# main.net
KiCad netlist of a schematic drawn in Altium Designer
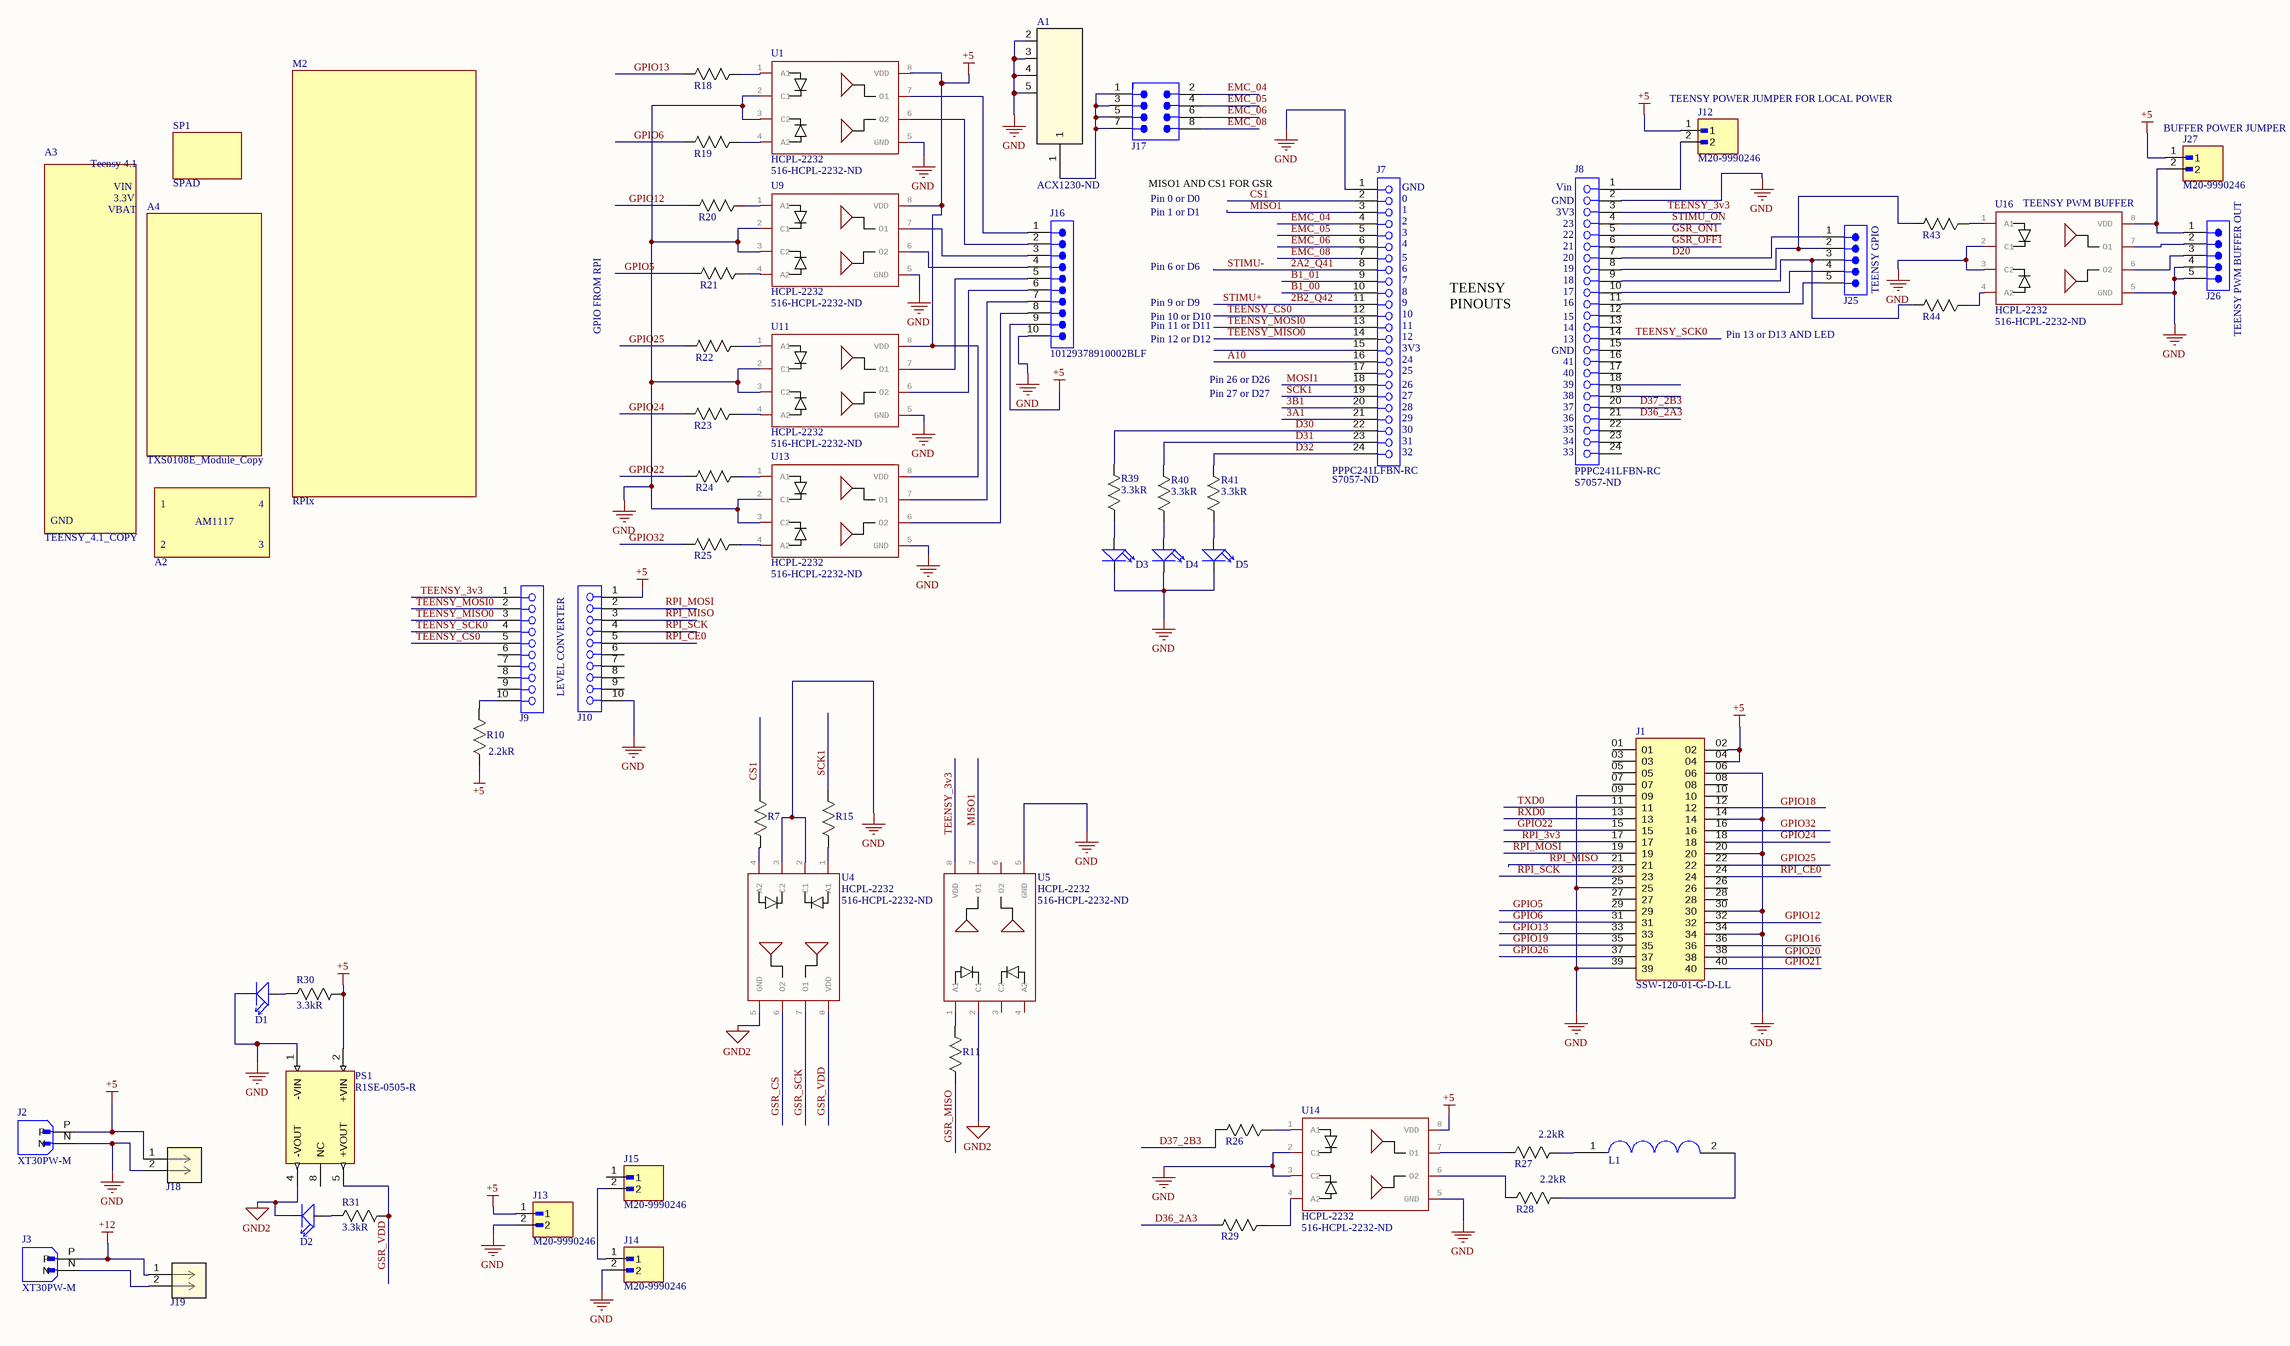
[diagram p0: main.SchDoc]

(export (version "E")
  (design (tool "Eeschema 10.0.6"))
  (components
    (comp (ref "A1")
      (value "SMA_VERTICAL")
      (footprint "SMA_VERTICAL")
      (description "connector, rf coaxial, sma str jack for p.c.board, 4 legs, .050 center cont, 50 ohm")
      (fields
        (field (name "MANUFACTURER") "Amphenol Connex")
        (field (name "MANUFACTURER PART NUMBER") "132134")
        (field (name "SUPPLIER PART NUMBER 1") "ACX1230-ND")
      )
      (libsource (lib "koncept") (part "SMA_VERTICAL"))
    )
    (comp (ref "A2")
      (value "AMS1117_BOARD_Copy")
      (footprint "AM117_BOARD_Copy")
      (libsource (lib "koncept") (part "AMS1117_BOARD_Copy"))
    )
    (comp (ref "A3")
      (value "TEENSY_4.1_COPY")
      (footprint "TEENSY_LONG_EXT_COPY")
      (fields (field (name "MF") "PJRC") (field (name "MP") "Teensy 4.1"))
      (libsource (lib "koncept") (part "TEENSY_4.1_COPY"))
    )
    (comp (ref "A4")
      (value "TXS0108E_Module_Copy")
      (footprint "TXS0108E_Module_Copy")
      (libsource (lib "koncept") (part "TXS0108E_Module_Copy"))
    )
    (comp (ref "D1")
      (value "LED")
      (footprint "LEDM1608X80")
      (description "Single Color LED, Ultra Bright Orange, Water Clear, 1.1mm")
      (fields
        (field (name "MANUFACTURER") "Vishay Lite-On")
        (field (name "MANUFACTURER PART NUMBER") "LTST-C190KFKT")
      )
      (libsource (lib "Passive") (part "LTST-C190KFKT_1"))
    )
    (comp (ref "D2")
      (value "LED")
      (footprint "LEDM1608X80")
      (description "Single Color LED, Ultra Bright Orange, Water Clear, 1.1mm")
      (fields
        (field (name "MANUFACTURER") "Vishay Lite-On")
        (field (name "MANUFACTURER PART NUMBER") "LTST-C190KFKT")
      )
      (libsource (lib "Passive") (part "LTST-C190KFKT_1"))
    )
    (comp (ref "D3")
      (value "LED")
      (footprint "LEDM1608X80")
      (description "Single Color LED, Ultra Bright Orange, Water Clear, 1.1mm")
      (fields
        (field (name "MANUFACTURER") "Vishay Lite-On")
        (field (name "MANUFACTURER PART NUMBER") "LTST-C190KFKT")
      )
      (libsource (lib "Passive") (part "LTST-C190KFKT_1"))
    )
    (comp (ref "D4")
      (value "LED")
      (footprint "LEDM1608X80")
      (description "Single Color LED, Ultra Bright Orange, Water Clear, 1.1mm")
      (fields
        (field (name "MANUFACTURER") "Vishay Lite-On")
        (field (name "MANUFACTURER PART NUMBER") "LTST-C190KFKT")
      )
      (libsource (lib "Passive") (part "LTST-C190KFKT_1"))
    )
    (comp (ref "D5")
      (value "LED")
      (footprint "LEDM1608X80")
      (description "Single Color LED, Ultra Bright Orange, Water Clear, 1.1mm")
      (fields
        (field (name "MANUFACTURER") "Vishay Lite-On")
        (field (name "MANUFACTURER PART NUMBER") "LTST-C190KFKT")
      )
      (libsource (lib "Passive") (part "LTST-C190KFKT_1"))
    )
    (comp (ref "J1")
      (value "SSW-120-01-G-D-LL")
      (footprint "SAMTEC_SSW-120-01-G-D-LL")
      (fields (field (name "MF") "Samtec Inc."))
      (libsource (lib "koncept") (part "SSW-120-01-G-D-LL"))
    )
    (comp (ref "J2")
      (value "XT30PW-M")
      (footprint "AMASS_XT30PW-M")
      (description "Socket; DC supply; XT30; male; PIN: 2; on PCBs; THT; Colour: yellow")
      (fields (field (name "MF") "AMASS"))
      (libsource (lib "koncept") (part "XT30PW-M"))
    )
    (comp (ref "J3")
      (value "XT30PW-M")
      (footprint "AMASS_XT30PW-M")
      (description "Socket; DC supply; XT30; male; PIN: 2; on PCBs; THT; Colour: yellow")
      (fields (field (name "MF") "AMASS"))
      (libsource (lib "koncept") (part "XT30PW-M"))
    )
    (comp (ref "J7")
      (value "PPPC241LFBN-RC")
      (footprint "HEADER_SOCKET_24")
      (description "Conn Hdr 24POS 0.1 Gold Pcb")
      (fields (field (name "MANUFACTURER") "Sullins") (field (name "SUPPLIER PART NUMBER 1") "S7057-ND"))
      (libsource (lib "Connectors") (part "HEADER_SOCKET_24"))
    )
    (comp (ref "J8")
      (value "PPPC241LFBN-RC")
      (footprint "HEADER_SOCKET_24")
      (description "Conn Hdr 24POS 0.1 Gold Pcb")
      (fields (field (name "MANUFACTURER") "Sullins") (field (name "SUPPLIER PART NUMBER 1") "S7057-ND"))
      (libsource (lib "Connectors") (part "HEADER_SOCKET_24"))
    )
    (comp (ref "J9")
      (value "PPTC101LFBN-RC")
      (footprint "HEADER_SOCKET_10")
      (description "10 Position Single Row 2.54 mm Pitch Vertical Through Hole Socket Header")
      (fields (field (name "MANUFACTURER") "Sullins"))
      (libsource (lib "Connectors") (part "HEADER_SOCKET_10"))
    )
    (comp (ref "J10")
      (value "PPTC101LFBN-RC")
      (footprint "HEADER_SOCKET_10")
      (description "10 Position Single Row 2.54 mm Pitch Vertical Through Hole Socket Header")
      (fields (field (name "MANUFACTURER") "Sullins"))
      (libsource (lib "Connectors") (part "HEADER_SOCKET_10"))
    )
    (comp (ref "J12")
      (value "M20-9990246")
      (footprint "HARWIN_M20-9990246")
      (description "2.54mm (0.1) Pitch SIL Vertical Throughboard Pin Header, 6.1mm mating pin height, tin, 2 contacts")
      (fields (field (name "MF") "Harwin"))
      (libsource (lib "koncept") (part "M20-9990246"))
    )
    (comp (ref "J13")
      (value "M20-9990246")
      (footprint "HARWIN_M20-9990246")
      (description "2.54mm (0.1) Pitch SIL Vertical Throughboard Pin Header, 6.1mm mating pin height, tin, 2 contacts")
      (fields (field (name "MF") "Harwin"))
      (libsource (lib "koncept") (part "M20-9990246"))
    )
    (comp (ref "J14")
      (value "M20-9990246")
      (footprint "HARWIN_M20-9990246")
      (description "2.54mm (0.1) Pitch SIL Vertical Throughboard Pin Header, 6.1mm mating pin height, tin, 2 contacts")
      (fields (field (name "MF") "Harwin"))
      (libsource (lib "koncept") (part "M20-9990246"))
    )
    (comp (ref "J15")
      (value "M20-9990246")
      (footprint "HARWIN_M20-9990246")
      (description "2.54mm (0.1) Pitch SIL Vertical Throughboard Pin Header, 6.1mm mating pin height, tin, 2 contacts")
      (fields (field (name "MF") "Harwin"))
      (libsource (lib "koncept") (part "M20-9990246"))
    )
    (comp (ref "J16")
      (value "10129378910002BLF")
      (footprint "HEADER_PIN_10")
      (description "Header Sr Vt Th 1X10-10129378-910002BLF")
      (fields (field (name "MANUFACTURER") "Amphenol ICC / FCI"))
      (libsource (lib "Connectors") (part "HEADER_PIN_10"))
    )
    (comp (ref "J17")
      (value "TSW-104-07-F-D")
      (footprint "HEADER_PIN_DOUBLE_8")
      (description "Connector, Header, 8Pos, 2Row, 2.54Mm Rohs Compliant: Yes")
      (fields (field (name "MANUFACTURER") "Samtec"))
      (libsource (lib "Connectors") (part "HEADER_PIN_DOUBLE_8"))
    )
    (comp (ref "J18")
      (value "B2P-VH")
      (footprint "CONN_B2P-VH_JST")
      (description "VH Non-RoHS Compliant 2003 Vertical Connector Header -25C~85C 10A 250V 0.303 7.70mm")
      (fields (field (name "MANUFACTURER") "JST"))
      (libsource (lib "Connectors") (part "B2P-VH"))
    )
    (comp (ref "J19")
      (value "B2P-VH")
      (footprint "CONN_B2P-VH_JST")
      (description "VH Non-RoHS Compliant 2003 Vertical Connector Header -25C~85C 10A 250V 0.303 7.70mm")
      (fields (field (name "MANUFACTURER") "JST"))
      (libsource (lib "Connectors") (part "B2P-VH"))
    )
    (comp (ref "J25")
      (value "61300511121")
      (footprint "HEADER_M_5")
      (description "THT Vertical Pin Header WR-PHD, Pitch 2.54 mm, Single Row, 5 pins")
      (fields (field (name "MANUFACTURER") "Wurth Electronics"))
      (libsource (lib "Connectors") (part "HEADER_M_5"))
    )
    (comp (ref "J26")
      (value "61300511121")
      (footprint "HEADER_M_5")
      (description "THT Vertical Pin Header WR-PHD, Pitch 2.54 mm, Single Row, 5 pins")
      (fields (field (name "MANUFACTURER") "Wurth Electronics"))
      (libsource (lib "Connectors") (part "HEADER_M_5"))
    )
    (comp (ref "J27")
      (value "M20-9990246")
      (footprint "HARWIN_M20-9990246")
      (description "2.54mm (0.1) Pitch SIL Vertical Throughboard Pin Header, 6.1mm mating pin height, tin, 2 contacts")
      (fields (field (name "MF") "Harwin"))
      (libsource (lib "koncept") (part "M20-9990246"))
    )
    (comp (ref "L1")
      (value "COIL_PLANNER_A")
      (footprint "COIL_PLANNER_A")
      (libsource (lib "koncept") (part "COIL_PLANNER_A"))
    )
    (comp (ref "M2")
      (value "RPIx")
      (footprint "MODULE_RASPBERRY_PI_3_COPY")
      (libsource (lib "koncept") (part "RPIx_Copy"))
    )
    (comp (ref "PS1")
      (value "R1SE-0505-R")
      (footprint "CONV_R1SE-0505-R")
      (description "1W DC/DC-Converter 'ECONOLINE' SMD 1kV unreg")
      (fields (field (name "MF") "Recom Power"))
      (libsource (lib "koncept") (part "R1SE-0505-R"))
    )
    (comp (ref "R7")
      (value "RMCF1206FT220R")
      (footprint "STA_RMCF1206_STP-L")
      (description "No Description Available")
      (fields (field (name "COPYRIGHT") "Copyright (C) 2025 Ultra Librarian. All rights reserved."))
      (libsource (lib "Passive") (part "RMCF1206FT220R"))
    )
    (comp (ref "R10")
      (value "CRGCQ1206F2K2")
      (footprint "STA_RMCF1206_STP-L")
      (description "SMD Chip Resistor, 2.2 kOhm, ± 1%, 250 mW, 1206 [3216 Metric], Thick Film, General Purpose")
      (fields (field (name "MANUFACTURER") "TE Connectivity") (field (name "RESISTANCE") "2.2kR"))
      (libsource (lib "Passive") (part "R1206F2K2"))
    )
    (comp (ref "R11")
      (value "RMCF1206FT220R")
      (footprint "STA_RMCF1206_STP-L")
      (description "No Description Available")
      (fields (field (name "COPYRIGHT") "Copyright (C) 2025 Ultra Librarian. All rights reserved."))
      (libsource (lib "Passive") (part "RMCF1206FT220R"))
    )
    (comp (ref "R15")
      (value "RMCF1206FT220R")
      (footprint "STA_RMCF1206_STP-L")
      (description "No Description Available")
      (fields (field (name "COPYRIGHT") "Copyright (C) 2025 Ultra Librarian. All rights reserved."))
      (libsource (lib "Passive") (part "RMCF1206FT220R"))
    )
    (comp (ref "R18")
      (value "RMCF1206FT220R")
      (footprint "STA_RMCF1206_STP-L")
      (description "No Description Available")
      (fields (field (name "COPYRIGHT") "Copyright (C) 2025 Ultra Librarian. All rights reserved."))
      (libsource (lib "Passive") (part "RMCF1206FT220R"))
    )
    (comp (ref "R19")
      (value "RMCF1206FT220R")
      (footprint "STA_RMCF1206_STP-L")
      (description "No Description Available")
      (fields (field (name "COPYRIGHT") "Copyright (C) 2025 Ultra Librarian. All rights reserved."))
      (libsource (lib "Passive") (part "RMCF1206FT220R"))
    )
    (comp (ref "R20")
      (value "RMCF1206FT220R")
      (footprint "STA_RMCF1206_STP-L")
      (description "No Description Available")
      (fields (field (name "COPYRIGHT") "Copyright (C) 2025 Ultra Librarian. All rights reserved."))
      (libsource (lib "Passive") (part "RMCF1206FT220R"))
    )
    (comp (ref "R21")
      (value "RMCF1206FT220R")
      (footprint "STA_RMCF1206_STP-L")
      (description "No Description Available")
      (fields (field (name "COPYRIGHT") "Copyright (C) 2025 Ultra Librarian. All rights reserved."))
      (libsource (lib "Passive") (part "RMCF1206FT220R"))
    )
    (comp (ref "R22")
      (value "RMCF1206FT220R")
      (footprint "STA_RMCF1206_STP-L")
      (description "No Description Available")
      (fields (field (name "COPYRIGHT") "Copyright (C) 2025 Ultra Librarian. All rights reserved."))
      (libsource (lib "Passive") (part "RMCF1206FT220R"))
    )
    (comp (ref "R23")
      (value "RMCF1206FT220R")
      (footprint "STA_RMCF1206_STP-L")
      (description "No Description Available")
      (fields (field (name "COPYRIGHT") "Copyright (C) 2025 Ultra Librarian. All rights reserved."))
      (libsource (lib "Passive") (part "RMCF1206FT220R"))
    )
    (comp (ref "R24")
      (value "RMCF1206FT220R")
      (footprint "STA_RMCF1206_STP-L")
      (description "No Description Available")
      (fields (field (name "COPYRIGHT") "Copyright (C) 2025 Ultra Librarian. All rights reserved."))
      (libsource (lib "Passive") (part "RMCF1206FT220R"))
    )
    (comp (ref "R25")
      (value "RMCF1206FT220R")
      (footprint "STA_RMCF1206_STP-L")
      (description "No Description Available")
      (fields (field (name "COPYRIGHT") "Copyright (C) 2025 Ultra Librarian. All rights reserved."))
      (libsource (lib "Passive") (part "RMCF1206FT220R"))
    )
    (comp (ref "R26")
      (value "RMCF1206FT220R")
      (footprint "STA_RMCF1206_STP-L")
      (description "No Description Available")
      (fields (field (name "COPYRIGHT") "Copyright (C) 2025 Ultra Librarian. All rights reserved."))
      (libsource (lib "Passive") (part "RMCF1206FT220R"))
    )
    (comp (ref "R27")
      (value "CRGCQ1206F2K2")
      (footprint "STA_RMCF1206_STP-L")
      (description "SMD Chip Resistor, 2.2 kOhm, ± 1%, 250 mW, 1206 [3216 Metric], Thick Film, General Purpose")
      (fields (field (name "MANUFACTURER") "TE Connectivity") (field (name "RESISTANCE") "2.2kR"))
      (libsource (lib "Passive") (part "R1206F2K2"))
    )
    (comp (ref "R28")
      (value "CRGCQ1206F2K2")
      (footprint "STA_RMCF1206_STP-L")
      (description "SMD Chip Resistor, 2.2 kOhm, ± 1%, 250 mW, 1206 [3216 Metric], Thick Film, General Purpose")
      (fields (field (name "MANUFACTURER") "TE Connectivity") (field (name "RESISTANCE") "2.2kR"))
      (libsource (lib "Passive") (part "R1206F2K2"))
    )
    (comp (ref "R29")
      (value "RMCF1206FT220R")
      (footprint "STA_RMCF1206_STP-L")
      (description "No Description Available")
      (fields (field (name "COPYRIGHT") "Copyright (C) 2025 Ultra Librarian. All rights reserved."))
      (libsource (lib "Passive") (part "RMCF1206FT220R"))
    )
    (comp (ref "R30")
      (value "CRG1206F3K3")
      (footprint "STA_RMCF1206_STP-L")
      (description "Res Thick Film 1206 3.3K Ohm 1% 0.25W(1/4W) ±100ppm/C Pad SMD T/R")
      (fields
        (field (name "MANUFACTURER") "TE Connectivity")
        (field (name "TOLERANCE") "1%")
        (field (name "RESISTANCE") "3.3kR")
      )
      (libsource (lib "Passive") (part "R3K3_1206"))
    )
    (comp (ref "R31")
      (value "CRG1206F3K3")
      (footprint "STA_RMCF1206_STP-L")
      (description "Res Thick Film 1206 3.3K Ohm 1% 0.25W(1/4W) ±100ppm/C Pad SMD T/R")
      (fields
        (field (name "MANUFACTURER") "TE Connectivity")
        (field (name "TOLERANCE") "1%")
        (field (name "RESISTANCE") "3.3kR")
      )
      (libsource (lib "Passive") (part "R3K3_1206"))
    )
    (comp (ref "R39")
      (value "CRG1206F3K3")
      (footprint "STA_RMCF1206_STP-L")
      (description "Res Thick Film 1206 3.3K Ohm 1% 0.25W(1/4W) ±100ppm/C Pad SMD T/R")
      (fields
        (field (name "MANUFACTURER") "TE Connectivity")
        (field (name "TOLERANCE") "1%")
        (field (name "RESISTANCE") "3.3kR")
      )
      (libsource (lib "Passive") (part "R3K3_1206"))
    )
    (comp (ref "R40")
      (value "CRG1206F3K3")
      (footprint "STA_RMCF1206_STP-L")
      (description "Res Thick Film 1206 3.3K Ohm 1% 0.25W(1/4W) ±100ppm/C Pad SMD T/R")
      (fields
        (field (name "MANUFACTURER") "TE Connectivity")
        (field (name "TOLERANCE") "1%")
        (field (name "RESISTANCE") "3.3kR")
      )
      (libsource (lib "Passive") (part "R3K3_1206"))
    )
    (comp (ref "R41")
      (value "CRG1206F3K3")
      (footprint "STA_RMCF1206_STP-L")
      (description "Res Thick Film 1206 3.3K Ohm 1% 0.25W(1/4W) ±100ppm/C Pad SMD T/R")
      (fields
        (field (name "MANUFACTURER") "TE Connectivity")
        (field (name "TOLERANCE") "1%")
        (field (name "RESISTANCE") "3.3kR")
      )
      (libsource (lib "Passive") (part "R3K3_1206"))
    )
    (comp (ref "R43")
      (value "RMCF1206FT220R")
      (footprint "STA_RMCF1206_STP-L")
      (description "No Description Available")
      (fields (field (name "COPYRIGHT") "Copyright (C) 2025 Ultra Librarian. All rights reserved."))
      (libsource (lib "Passive") (part "RMCF1206FT220R"))
    )
    (comp (ref "R44")
      (value "RMCF1206FT220R")
      (footprint "STA_RMCF1206_STP-L")
      (description "No Description Available")
      (fields (field (name "COPYRIGHT") "Copyright (C) 2025 Ultra Librarian. All rights reserved."))
      (libsource (lib "Passive") (part "RMCF1206FT220R"))
    )
    (comp (ref "SP1") (value "SPAD") (footprint "SPAD") (libsource (lib "koncept") (part "SPAD")))
    (comp (ref "U1")
      (value "HCPL-2232")
      (footprint "DIL08")
      (description "Optocoupler Logic Output Totem-Pole DC Input 2 Channel 8-Pin Plastic Dip Tube")
      (fields
        (field (name "MANUFACTURER") "Broadcom Avago")
        (field (name "SUPPLIER PART NUMBER 1") "516-HCPL-2232-ND")
      )
      (libsource (lib "koncept") (part "HCPL-2232"))
    )
    (comp (ref "U4")
      (value "HCPL-2232")
      (footprint "DIL08")
      (description "Optocoupler Logic Output Totem-Pole DC Input 2 Channel 8-Pin Plastic Dip Tube")
      (fields
        (field (name "MANUFACTURER") "Broadcom Avago")
        (field (name "SUPPLIER PART NUMBER 1") "516-HCPL-2232-ND")
      )
      (libsource (lib "koncept") (part "HCPL-2232"))
    )
    (comp (ref "U5")
      (value "HCPL-2232")
      (footprint "DIL08")
      (description "Optocoupler Logic Output Totem-Pole DC Input 2 Channel 8-Pin Plastic Dip Tube")
      (fields
        (field (name "MANUFACTURER") "Broadcom Avago")
        (field (name "SUPPLIER PART NUMBER 1") "516-HCPL-2232-ND")
      )
      (libsource (lib "koncept") (part "HCPL-2232"))
    )
    (comp (ref "U9")
      (value "HCPL-2232")
      (footprint "DIL08")
      (description "Optocoupler Logic Output Totem-Pole DC Input 2 Channel 8-Pin Plastic Dip Tube")
      (fields
        (field (name "MANUFACTURER") "Broadcom Avago")
        (field (name "SUPPLIER PART NUMBER 1") "516-HCPL-2232-ND")
      )
      (libsource (lib "koncept") (part "HCPL-2232"))
    )
    (comp (ref "U11")
      (value "HCPL-2232")
      (footprint "DIL08")
      (description "Optocoupler Logic Output Totem-Pole DC Input 2 Channel 8-Pin Plastic Dip Tube")
      (fields
        (field (name "MANUFACTURER") "Broadcom Avago")
        (field (name "SUPPLIER PART NUMBER 1") "516-HCPL-2232-ND")
      )
      (libsource (lib "koncept") (part "HCPL-2232"))
    )
    (comp (ref "U13")
      (value "HCPL-2232")
      (footprint "DIL08")
      (description "Optocoupler Logic Output Totem-Pole DC Input 2 Channel 8-Pin Plastic Dip Tube")
      (fields
        (field (name "MANUFACTURER") "Broadcom Avago")
        (field (name "SUPPLIER PART NUMBER 1") "516-HCPL-2232-ND")
      )
      (libsource (lib "koncept") (part "HCPL-2232"))
    )
    (comp (ref "U14")
      (value "HCPL-2232")
      (footprint "DIL08")
      (description "Optocoupler Logic Output Totem-Pole DC Input 2 Channel 8-Pin Plastic Dip Tube")
      (fields
        (field (name "MANUFACTURER") "Broadcom Avago")
        (field (name "SUPPLIER PART NUMBER 1") "516-HCPL-2232-ND")
      )
      (libsource (lib "koncept") (part "HCPL-2232"))
    )
    (comp (ref "U16")
      (value "HCPL-2232")
      (footprint "DIL08")
      (description "Optocoupler Logic Output Totem-Pole DC Input 2 Channel 8-Pin Plastic Dip Tube")
      (fields
        (field (name "MANUFACTURER") "Broadcom Avago")
        (field (name "SUPPLIER PART NUMBER 1") "516-HCPL-2232-ND")
      )
      (libsource (lib "koncept") (part "HCPL-2232"))
    )
  )
  (nets
    (net (code "1") (name "+5") (class "Default")
      (node (ref "J1") (pin "02") (pinfunction "02_02") (pintype "passive"))
      (node (ref "J1") (pin "04") (pinfunction "04_04") (pintype "passive"))
      (node (ref "J10") (pin "1") (pinfunction "1_1") (pintype "passive"))
      (node (ref "J12") (pin "1") (pinfunction "1_1") (pintype "passive"))
      (node (ref "J13") (pin "1") (pinfunction "1_1") (pintype "passive"))
      (node (ref "J16") (pin "9") (pinfunction "9_9") (pintype "passive"))
      (node (ref "J18") (pin "1") (pinfunction "1_1") (pintype "passive"))
      (node (ref "J2") (pin "P") (pinfunction "P_P") (pintype "power_in"))
      (node (ref "J27") (pin "1") (pinfunction "1_1") (pintype "passive"))
      (node (ref "PS1") (pin "2") (pinfunction "+VIN_2") (pintype "input"))
      (node (ref "R10") (pin "1") (pinfunction "1_1") (pintype "passive"))
      (node (ref "R30") (pin "2") (pinfunction "2_2") (pintype "passive"))
      (node (ref "U1") (pin "8") (pinfunction "VDD_8") (pintype "power_in"))
      (node (ref "U11") (pin "8") (pinfunction "VDD_8") (pintype "power_in"))
      (node (ref "U13") (pin "8") (pinfunction "VDD_8") (pintype "power_in"))
      (node (ref "U14") (pin "8") (pinfunction "VDD_8") (pintype "power_in"))
      (node (ref "U9") (pin "8") (pinfunction "VDD_8") (pintype "power_in"))
    )
    (net (code "2") (name "+12") (class "Default")
      (node (ref "J19") (pin "1") (pinfunction "1_1") (pintype "passive"))
      (node (ref "J3") (pin "P") (pinfunction "P_P") (pintype "power_in"))
    )
    (net (code "3") (name "/2A2_Q41") (class "Default")
      (node (ref "J7") (pin "8") (pinfunction "8_8") (pintype "passive"))
    )
    (net (code "4") (name "/2B2_Q42") (class "Default")
      (node (ref "J7") (pin "11") (pinfunction "11_11") (pintype "passive"))
    )
    (net (code "5") (name "/3A1") (class "Default")
      (node (ref "J7") (pin "21") (pinfunction "21_21") (pintype "passive"))
    )
    (net (code "6") (name "/3B1") (class "Default")
      (node (ref "J7") (pin "20") (pinfunction "20_20") (pintype "passive"))
    )
    (net (code "7") (name "/A10") (class "Default")
      (node (ref "J7") (pin "16") (pinfunction "16_16") (pintype "passive"))
    )
    (net (code "8") (name "/B1_00") (class "Default")
      (node (ref "J7") (pin "10") (pinfunction "10_10") (pintype "passive"))
    )
    (net (code "9") (name "/B1_01") (class "Default")
      (node (ref "J7") (pin "9") (pinfunction "9_9") (pintype "passive"))
    )
    (net (code "10") (name "/CS1") (class "Default")
      (node (ref "J7") (pin "2") (pinfunction "2_2") (pintype "passive"))
      (node (ref "R7") (pin "2") (pinfunction "2_2") (pintype "passive"))
    )
    (net (code "11") (name "/D20") (class "Default")
      (node (ref "J25") (pin "1") (pinfunction "1_1") (pintype "passive"))
      (node (ref "J8") (pin "7") (pinfunction "7_7") (pintype "passive"))
    )
    (net (code "12") (name "/D30") (class "Default")
      (node (ref "J7") (pin "22") (pinfunction "22_22") (pintype "passive"))
      (node (ref "R39") (pin "2") (pinfunction "2_2") (pintype "passive"))
    )
    (net (code "13") (name "/D31") (class "Default")
      (node (ref "J7") (pin "23") (pinfunction "23_23") (pintype "passive"))
      (node (ref "R40") (pin "2") (pinfunction "2_2") (pintype "passive"))
    )
    (net (code "14") (name "/D32") (class "Default")
      (node (ref "J7") (pin "24") (pinfunction "24_24") (pintype "passive"))
      (node (ref "R41") (pin "2") (pinfunction "2_2") (pintype "passive"))
    )
    (net (code "15") (name "/D36_2A3") (class "Default")
      (node (ref "J8") (pin "21") (pinfunction "21_21") (pintype "passive"))
      (node (ref "R29") (pin "2") (pinfunction "2_2") (pintype "passive"))
    )
    (net (code "16") (name "/D37_2B3") (class "Default")
      (node (ref "J8") (pin "20") (pinfunction "20_20") (pintype "passive"))
      (node (ref "R26") (pin "2") (pinfunction "2_2") (pintype "passive"))
    )
    (net (code "17") (name "/EMC_04") (class "Default")
      (node (ref "J17") (pin "2") (pinfunction "2_2") (pintype "passive"))
      (node (ref "J7") (pin "4") (pinfunction "4_4") (pintype "passive"))
    )
    (net (code "18") (name "/EMC_05") (class "Default")
      (node (ref "J17") (pin "4") (pinfunction "4_4") (pintype "passive"))
      (node (ref "J7") (pin "5") (pinfunction "5_5") (pintype "passive"))
    )
    (net (code "19") (name "/EMC_06") (class "Default")
      (node (ref "J17") (pin "6") (pinfunction "6_6") (pintype "passive"))
      (node (ref "J7") (pin "6") (pinfunction "6_6") (pintype "passive"))
    )
    (net (code "20") (name "/EMC_08") (class "Default")
      (node (ref "J17") (pin "8") (pinfunction "8_8") (pintype "passive"))
      (node (ref "J7") (pin "7") (pinfunction "7_7") (pintype "passive"))
    )
    (net (code "21") (name "/GPIO5") (class "Default")
      (node (ref "J1") (pin "29") (pinfunction "29_29") (pintype "passive"))
      (node (ref "R21") (pin "2") (pinfunction "2_2") (pintype "passive"))
    )
    (net (code "22") (name "/GPIO6") (class "Default")
      (node (ref "J1") (pin "31") (pinfunction "31_31") (pintype "passive"))
      (node (ref "R19") (pin "2") (pinfunction "2_2") (pintype "passive"))
    )
    (net (code "23") (name "/GPIO12") (class "Default")
      (node (ref "J1") (pin "32") (pinfunction "32_32") (pintype "passive"))
      (node (ref "R20") (pin "2") (pinfunction "2_2") (pintype "passive"))
    )
    (net (code "24") (name "/GPIO13") (class "Default")
      (node (ref "J1") (pin "33") (pinfunction "33_33") (pintype "passive"))
      (node (ref "R18") (pin "2") (pinfunction "2_2") (pintype "passive"))
    )
    (net (code "25") (name "/GPIO16") (class "Default")
      (node (ref "J1") (pin "36") (pinfunction "36_36") (pintype "passive"))
    )
    (net (code "27") (name "/GPIO19") (class "Default")
      (node (ref "J1") (pin "35") (pinfunction "35_35") (pintype "passive"))
    )
    (net (code "29") (name "/GPIO21") (class "Default")
      (node (ref "J1") (pin "40") (pinfunction "40_40") (pintype "passive"))
    )
    (net (code "30") (name "/GPIO22") (class "Default")
      (node (ref "J1") (pin "15") (pinfunction "15_15") (pintype "passive"))
      (node (ref "R24") (pin "2") (pinfunction "2_2") (pintype "passive"))
    )
    (net (code "31") (name "/GPIO24") (class "Default")
      (node (ref "J1") (pin "18") (pinfunction "18_18") (pintype "passive"))
      (node (ref "R23") (pin "2") (pinfunction "2_2") (pintype "passive"))
    )
    (net (code "32") (name "/GPIO25") (class "Default")
      (node (ref "J1") (pin "22") (pinfunction "22_22") (pintype "passive"))
      (node (ref "R22") (pin "2") (pinfunction "2_2") (pintype "passive"))
    )
    (net (code "33") (name "/GPIO26") (class "Default")
      (node (ref "J1") (pin "37") (pinfunction "37_37") (pintype "passive"))
    )
    (net (code "34") (name "/GPIO32") (class "Default")
      (node (ref "J1") (pin "16") (pinfunction "16_16") (pintype "passive"))
      (node (ref "R25") (pin "2") (pinfunction "2_2") (pintype "passive"))
    )
    (net (code "35") (name "/GSR_CS") (class "Default")
      (node (ref "U4") (pin "6") (pinfunction "O2_6") (pintype "power_in"))
    )
    (net (code "36") (name "/GSR_MISO") (class "Default")
      (node (ref "R11") (pin "1") (pinfunction "1_1") (pintype "passive"))
    )
    (net (code "37") (name "/GSR_OFF1") (class "Default")
      (node (ref "J8") (pin "6") (pinfunction "6_6") (pintype "passive"))
    )
    (net (code "38") (name "/GSR_ON1") (class "Default")
      (node (ref "J8") (pin "5") (pinfunction "5_5") (pintype "passive"))
    )
    (net (code "39") (name "/GSR_SCK") (class "Default")
      (node (ref "U4") (pin "7") (pinfunction "O1_7") (pintype "power_in"))
    )
    (net (code "40") (name "/GSR_VDD") (class "Default")
      (node (ref "PS1") (pin "5") (pinfunction "+VOUT_5") (pintype "output"))
      (node (ref "R31") (pin "2") (pinfunction "2_2") (pintype "passive"))
      (node (ref "U4") (pin "8") (pinfunction "VDD_8") (pintype "power_in"))
    )
    (net (code "41") (name "/MISO1") (class "Default")
      (node (ref "J7") (pin "3") (pinfunction "3_3") (pintype "passive"))
      (node (ref "U5") (pin "7") (pinfunction "O1_7") (pintype "power_in"))
    )
    (net (code "42") (name "/MOSI1") (class "Default")
      (node (ref "J7") (pin "18") (pinfunction "18_18") (pintype "passive"))
    )
    (net (code "43") (name "/RPI_3v3") (class "Default")
      (node (ref "J1") (pin "17") (pinfunction "17_17") (pintype "passive"))
    )
    (net (code "44") (name "/RPI_CE0") (class "Default")
      (node (ref "J1") (pin "24") (pinfunction "24_24") (pintype "passive"))
      (node (ref "J10") (pin "5") (pinfunction "5_5") (pintype "passive"))
    )
    (net (code "45") (name "/RPI_MISO") (class "Default")
      (node (ref "J1") (pin "21") (pinfunction "21_21") (pintype "passive"))
      (node (ref "J10") (pin "3") (pinfunction "3_3") (pintype "passive"))
    )
    (net (code "46") (name "/RPI_MOSI") (class "Default")
      (node (ref "J1") (pin "19") (pinfunction "19_19") (pintype "passive"))
      (node (ref "J10") (pin "2") (pinfunction "2_2") (pintype "passive"))
    )
    (net (code "47") (name "/RPI_SCK") (class "Default")
      (node (ref "J1") (pin "23") (pinfunction "23_23") (pintype "passive"))
      (node (ref "J10") (pin "4") (pinfunction "4_4") (pintype "passive"))
    )
    (net (code "48") (name "/RXD0") (class "Default")
      (node (ref "J1") (pin "13") (pinfunction "13_13") (pintype "passive"))
    )
    (net (code "49") (name "/SCK1") (class "Default")
      (node (ref "J7") (pin "19") (pinfunction "19_19") (pintype "passive"))
      (node (ref "R15") (pin "2") (pinfunction "2_2") (pintype "passive"))
    )
    (net (code "50") (name "/STIMU_ON") (class "Default")
      (node (ref "J8") (pin "4") (pinfunction "4_4") (pintype "passive"))
    )
    (net (code "51") (name "/TEENSY_3v3") (class "Default")
      (node (ref "J8") (pin "3") (pinfunction "3_3") (pintype "passive"))
      (node (ref "J9") (pin "1") (pinfunction "1_1") (pintype "passive"))
      (node (ref "U5") (pin "8") (pinfunction "VDD_8") (pintype "power_in"))
    )
    (net (code "52") (name "/TEENSY_CS0") (class "Default")
      (node (ref "J7") (pin "12") (pinfunction "12_12") (pintype "passive"))
      (node (ref "J9") (pin "5") (pinfunction "5_5") (pintype "passive"))
    )
    (net (code "53") (name "/TEENSY_MISO0") (class "Default")
      (node (ref "J7") (pin "14") (pinfunction "14_14") (pintype "passive"))
      (node (ref "J9") (pin "3") (pinfunction "3_3") (pintype "passive"))
    )
    (net (code "54") (name "/TEENSY_MOSI0") (class "Default")
      (node (ref "J7") (pin "13") (pinfunction "13_13") (pintype "passive"))
      (node (ref "J9") (pin "2") (pinfunction "2_2") (pintype "passive"))
    )
    (net (code "55") (name "/TEENSY_SCK0") (class "Default")
      (node (ref "J8") (pin "14") (pinfunction "14_14") (pintype "passive"))
      (node (ref "J9") (pin "4") (pinfunction "4_4") (pintype "passive"))
    )
    (net (code "56") (name "/TXD0") (class "Default")
      (node (ref "J1") (pin "11") (pinfunction "11_11") (pintype "passive"))
    )
    (net (code "57") (name "GND") (class "Default")
      (node (ref "A1") (pin "2") (pinfunction "2_2") (pintype "passive"))
      (node (ref "A1") (pin "3") (pinfunction "3_3") (pintype "passive"))
      (node (ref "A1") (pin "4") (pinfunction "4_4") (pintype "passive"))
      (node (ref "A1") (pin "5") (pinfunction "5_5") (pintype "passive"))
      (node (ref "D1") (pin "C") (pinfunction "C_C") (pintype "passive"))
      (node (ref "D3") (pin "C") (pinfunction "C_C") (pintype "passive"))
      (node (ref "D4") (pin "C") (pinfunction "C_C") (pintype "passive"))
      (node (ref "D5") (pin "C") (pinfunction "C_C") (pintype "passive"))
      (node (ref "J1") (pin "06") (pinfunction "06_06") (pintype "passive"))
      (node (ref "J1") (pin "09") (pinfunction "09_09") (pintype "passive"))
      (node (ref "J1") (pin "14") (pinfunction "14_14") (pintype "passive"))
      (node (ref "J1") (pin "20") (pinfunction "20_20") (pintype "passive"))
      (node (ref "J1") (pin "25") (pinfunction "25_25") (pintype "passive"))
      (node (ref "J1") (pin "30") (pinfunction "30_30") (pintype "passive"))
      (node (ref "J1") (pin "34") (pinfunction "34_34") (pintype "passive"))
      (node (ref "J1") (pin "39") (pinfunction "39_39") (pintype "passive"))
      (node (ref "J10") (pin "10") (pinfunction "10_10") (pintype "passive"))
      (node (ref "J13") (pin "2") (pinfunction "2_2") (pintype "passive"))
      (node (ref "J14") (pin "2") (pinfunction "2_2") (pintype "passive"))
      (node (ref "J16") (pin "10") (pinfunction "10_10") (pintype "passive"))
      (node (ref "J18") (pin "2") (pinfunction "2_2") (pintype "passive"))
      (node (ref "J2") (pin "N") (pinfunction "N_N") (pintype "power_in"))
      (node (ref "J26") (pin "4") (pinfunction "4_4") (pintype "passive"))
      (node (ref "J26") (pin "5") (pinfunction "5_5") (pintype "passive"))
      (node (ref "J7") (pin "1") (pinfunction "1_1") (pintype "passive"))
      (node (ref "J8") (pin "2") (pinfunction "2_2") (pintype "passive"))
      (node (ref "PS1") (pin "1") (pinfunction "-VIN_1") (pintype "input"))
      (node (ref "U1") (pin "2") (pinfunction "C1_2") (pintype "power_in"))
      (node (ref "U1") (pin "3") (pinfunction "C2_3") (pintype "power_in"))
      (node (ref "U1") (pin "5") (pinfunction "GND_5") (pintype "power_in"))
      (node (ref "U11") (pin "2") (pinfunction "C1_2") (pintype "power_in"))
      (node (ref "U11") (pin "3") (pinfunction "C2_3") (pintype "power_in"))
      (node (ref "U11") (pin "5") (pinfunction "GND_5") (pintype "power_in"))
      (node (ref "U13") (pin "2") (pinfunction "C1_2") (pintype "power_in"))
      (node (ref "U13") (pin "3") (pinfunction "C2_3") (pintype "power_in"))
      (node (ref "U13") (pin "5") (pinfunction "GND_5") (pintype "power_in"))
      (node (ref "U14") (pin "2") (pinfunction "C1_2") (pintype "power_in"))
      (node (ref "U14") (pin "3") (pinfunction "C2_3") (pintype "power_in"))
      (node (ref "U14") (pin "5") (pinfunction "GND_5") (pintype "power_in"))
      (node (ref "U16") (pin "2") (pinfunction "C1_2") (pintype "power_in"))
      (node (ref "U16") (pin "3") (pinfunction "C2_3") (pintype "power_in"))
      (node (ref "U16") (pin "5") (pinfunction "GND_5") (pintype "power_in"))
      (node (ref "U4") (pin "2") (pinfunction "C1_2") (pintype "power_in"))
      (node (ref "U4") (pin "3") (pinfunction "C2_3") (pintype "power_in"))
      (node (ref "U5") (pin "5") (pinfunction "GND_5") (pintype "power_in"))
      (node (ref "U9") (pin "2") (pinfunction "C1_2") (pintype "power_in"))
      (node (ref "U9") (pin "3") (pinfunction "C2_3") (pintype "power_in"))
      (node (ref "U9") (pin "5") (pinfunction "GND_5") (pintype "power_in"))
    )
    (net (code "58") (name "GND2") (class "Default")
      (node (ref "D2") (pin "C") (pinfunction "C_C") (pintype "passive"))
      (node (ref "PS1") (pin "4") (pinfunction "-VOUT_4") (pintype "output"))
      (node (ref "U4") (pin "5") (pinfunction "GND_5") (pintype "power_in"))
      (node (ref "U5") (pin "2") (pinfunction "C1_2") (pintype "power_in"))
    )
    (net (code "59") (name "Net-(A1-Pad1)") (class "Default")
      (node (ref "A1") (pin "1") (pinfunction "1_1") (pintype "passive"))
      (node (ref "J17") (pin "1") (pinfunction "1_1") (pintype "passive"))
      (node (ref "J17") (pin "3") (pinfunction "3_3") (pintype "passive"))
      (node (ref "J17") (pin "5") (pinfunction "5_5") (pintype "passive"))
      (node (ref "J17") (pin "7") (pinfunction "7_7") (pintype "passive"))
    )
    (net (code "60") (name "Net-(D1-PadA)") (class "Default")
      (node (ref "D1") (pin "A") (pinfunction "A_A") (pintype "passive"))
      (node (ref "R30") (pin "1") (pinfunction "1_1") (pintype "passive"))
    )
    (net (code "61") (name "Net-(D2-PadA)") (class "Default")
      (node (ref "D2") (pin "A") (pinfunction "A_A") (pintype "passive"))
      (node (ref "R31") (pin "1") (pinfunction "1_1") (pintype "passive"))
    )
    (net (code "62") (name "Net-(D3-PadA)") (class "Default")
      (node (ref "D3") (pin "A") (pinfunction "A_A") (pintype "passive"))
      (node (ref "R39") (pin "1") (pinfunction "1_1") (pintype "passive"))
    )
    (net (code "63") (name "Net-(D4-PadA)") (class "Default")
      (node (ref "D4") (pin "A") (pinfunction "A_A") (pintype "passive"))
      (node (ref "R40") (pin "1") (pinfunction "1_1") (pintype "passive"))
    )
    (net (code "64") (name "Net-(D5-PadA)") (class "Default")
      (node (ref "D5") (pin "A") (pinfunction "A_A") (pintype "passive"))
      (node (ref "R41") (pin "1") (pinfunction "1_1") (pintype "passive"))
    )
    (net (code "65") (name "Net-(J9-Pad10)") (class "Default")
      (node (ref "J9") (pin "10") (pinfunction "10_10") (pintype "passive"))
      (node (ref "R10") (pin "2") (pinfunction "2_2") (pintype "passive"))
    )
    (net (code "66") (name "Net-(J12-Pad2)") (class "Default")
      (node (ref "J12") (pin "2") (pinfunction "2_2") (pintype "passive"))
      (node (ref "J8") (pin "1") (pinfunction "1_1") (pintype "passive"))
    )
    (net (code "67") (name "Net-(J14-Pad1)") (class "Default")
      (node (ref "J14") (pin "1") (pinfunction "1_1") (pintype "passive"))
      (node (ref "J15") (pin "2") (pinfunction "2_2") (pintype "passive"))
    )
    (net (code "68") (name "Net-(J19-Pad2)") (class "Default")
      (node (ref "J19") (pin "2") (pinfunction "2_2") (pintype "passive"))
      (node (ref "J3") (pin "N") (pinfunction "N_N") (pintype "power_in"))
    )
    (net (code "69") (name "Net-(J25-Pad2)") (class "Default")
      (node (ref "J25") (pin "2") (pinfunction "2_2") (pintype "passive"))
      (node (ref "J8") (pin "8") (pinfunction "8_8") (pintype "passive"))
      (node (ref "R43") (pin "2") (pinfunction "2_2") (pintype "passive"))
    )
    (net (code "70") (name "Net-(J25-Pad3)") (class "Default")
      (node (ref "J25") (pin "3") (pinfunction "3_3") (pintype "passive"))
      (node (ref "J8") (pin "9") (pinfunction "9_9") (pintype "passive"))
      (node (ref "R44") (pin "2") (pinfunction "2_2") (pintype "passive"))
    )
    (net (code "71") (name "Net-(J25-Pad4)") (class "Default")
      (node (ref "J25") (pin "4") (pinfunction "4_4") (pintype "passive"))
      (node (ref "J8") (pin "10") (pinfunction "10_10") (pintype "passive"))
    )
    (net (code "72") (name "Net-(J25-Pad5)") (class "Default")
      (node (ref "J25") (pin "5") (pinfunction "5_5") (pintype "passive"))
      (node (ref "J8") (pin "11") (pinfunction "11_11") (pintype "passive"))
    )
    (net (code "73") (name "Net-(L1-Pad1)") (class "Default")
      (node (ref "L1") (pin "1") (pinfunction "1_1") (pintype "passive"))
      (node (ref "R27") (pin "2") (pinfunction "2_2") (pintype "passive"))
    )
    (net (code "74") (name "Net-(L1-Pad2)") (class "Default")
      (node (ref "L1") (pin "2") (pinfunction "2_2") (pintype "passive"))
      (node (ref "R28") (pin "2") (pinfunction "2_2") (pintype "passive"))
    )
    (net (code "75") (name "Net-(U1-A1)") (class "Default")
      (node (ref "R18") (pin "1") (pinfunction "1_1") (pintype "passive"))
      (node (ref "U1") (pin "1") (pinfunction "A1_1") (pintype "power_in"))
    )
    (net (code "76") (name "Net-(U1-A2)") (class "Default")
      (node (ref "R19") (pin "1") (pinfunction "1_1") (pintype "passive"))
      (node (ref "U1") (pin "4") (pinfunction "A2_4") (pintype "power_in"))
    )
    (net (code "77") (name "Net-(U1-O1)") (class "Default")
      (node (ref "J16") (pin "1") (pinfunction "1_1") (pintype "passive"))
      (node (ref "U1") (pin "7") (pinfunction "O1_7") (pintype "power_in"))
    )
    (net (code "78") (name "Net-(U1-O2)") (class "Default")
      (node (ref "J16") (pin "2") (pinfunction "2_2") (pintype "passive"))
      (node (ref "U1") (pin "6") (pinfunction "O2_6") (pintype "power_in"))
    )
    (net (code "79") (name "Net-(U4-A1)") (class "Default")
      (node (ref "R15") (pin "1") (pinfunction "1_1") (pintype "passive"))
      (node (ref "U4") (pin "1") (pinfunction "A1_1") (pintype "power_in"))
    )
    (net (code "80") (name "Net-(U4-A2)") (class "Default")
      (node (ref "R7") (pin "1") (pinfunction "1_1") (pintype "passive"))
      (node (ref "U4") (pin "4") (pinfunction "A2_4") (pintype "power_in"))
    )
    (net (code "81") (name "Net-(U5-A1)") (class "Default")
      (node (ref "R11") (pin "2") (pinfunction "2_2") (pintype "passive"))
      (node (ref "U5") (pin "1") (pinfunction "A1_1") (pintype "power_in"))
    )
    (net (code "82") (name "Net-(U9-A1)") (class "Default")
      (node (ref "R20") (pin "1") (pinfunction "1_1") (pintype "passive"))
      (node (ref "U9") (pin "1") (pinfunction "A1_1") (pintype "power_in"))
    )
    (net (code "83") (name "Net-(U9-A2)") (class "Default")
      (node (ref "R21") (pin "1") (pinfunction "1_1") (pintype "passive"))
      (node (ref "U9") (pin "4") (pinfunction "A2_4") (pintype "power_in"))
    )
    (net (code "84") (name "Net-(U9-O1)") (class "Default")
      (node (ref "J16") (pin "3") (pinfunction "3_3") (pintype "passive"))
      (node (ref "U9") (pin "7") (pinfunction "O1_7") (pintype "power_in"))
    )
    (net (code "85") (name "Net-(U9-O2)") (class "Default")
      (node (ref "J16") (pin "4") (pinfunction "4_4") (pintype "passive"))
      (node (ref "U9") (pin "6") (pinfunction "O2_6") (pintype "power_in"))
    )
    (net (code "86") (name "Net-(U11-A1)") (class "Default")
      (node (ref "R22") (pin "1") (pinfunction "1_1") (pintype "passive"))
      (node (ref "U11") (pin "1") (pinfunction "A1_1") (pintype "power_in"))
    )
    (net (code "87") (name "Net-(U11-A2)") (class "Default")
      (node (ref "R23") (pin "1") (pinfunction "1_1") (pintype "passive"))
      (node (ref "U11") (pin "4") (pinfunction "A2_4") (pintype "power_in"))
    )
    (net (code "88") (name "Net-(U11-O1)") (class "Default")
      (node (ref "J16") (pin "5") (pinfunction "5_5") (pintype "passive"))
      (node (ref "U11") (pin "7") (pinfunction "O1_7") (pintype "power_in"))
    )
    (net (code "89") (name "Net-(U11-O2)") (class "Default")
      (node (ref "J16") (pin "6") (pinfunction "6_6") (pintype "passive"))
      (node (ref "U11") (pin "6") (pinfunction "O2_6") (pintype "power_in"))
    )
    (net (code "90") (name "Net-(U13-A1)") (class "Default")
      (node (ref "R24") (pin "1") (pinfunction "1_1") (pintype "passive"))
      (node (ref "U13") (pin "1") (pinfunction "A1_1") (pintype "power_in"))
    )
    (net (code "91") (name "Net-(U13-A2)") (class "Default")
      (node (ref "R25") (pin "1") (pinfunction "1_1") (pintype "passive"))
      (node (ref "U13") (pin "4") (pinfunction "A2_4") (pintype "power_in"))
    )
    (net (code "92") (name "Net-(U13-O1)") (class "Default")
      (node (ref "J16") (pin "7") (pinfunction "7_7") (pintype "passive"))
      (node (ref "U13") (pin "7") (pinfunction "O1_7") (pintype "power_in"))
    )
    (net (code "93") (name "Net-(U13-O2)") (class "Default")
      (node (ref "J16") (pin "8") (pinfunction "8_8") (pintype "passive"))
      (node (ref "U13") (pin "6") (pinfunction "O2_6") (pintype "power_in"))
    )
    (net (code "94") (name "Net-(U14-A1)") (class "Default")
      (node (ref "R26") (pin "1") (pinfunction "1_1") (pintype "passive"))
      (node (ref "U14") (pin "1") (pinfunction "A1_1") (pintype "power_in"))
    )
    (net (code "95") (name "Net-(U14-A2)") (class "Default")
      (node (ref "R29") (pin "1") (pinfunction "1_1") (pintype "passive"))
      (node (ref "U14") (pin "4") (pinfunction "A2_4") (pintype "power_in"))
    )
    (net (code "96") (name "Net-(U14-O1)") (class "Default")
      (node (ref "R27") (pin "1") (pinfunction "1_1") (pintype "passive"))
      (node (ref "U14") (pin "7") (pinfunction "O1_7") (pintype "power_in"))
    )
    (net (code "97") (name "Net-(U14-O2)") (class "Default")
      (node (ref "R28") (pin "1") (pinfunction "1_1") (pintype "passive"))
      (node (ref "U14") (pin "6") (pinfunction "O2_6") (pintype "power_in"))
    )
    (net (code "98") (name "Net-(U16-A1)") (class "Default")
      (node (ref "R43") (pin "1") (pinfunction "1_1") (pintype "passive"))
      (node (ref "U16") (pin "1") (pinfunction "A1_1") (pintype "power_in"))
    )
    (net (code "99") (name "Net-(U16-A2)") (class "Default")
      (node (ref "R44") (pin "1") (pinfunction "1_1") (pintype "passive"))
      (node (ref "U16") (pin "4") (pinfunction "A2_4") (pintype "power_in"))
    )
    (net (code "100") (name "Net-(U16-O1)") (class "Default")
      (node (ref "J26") (pin "2") (pinfunction "2_2") (pintype "passive"))
      (node (ref "U16") (pin "7") (pinfunction "O1_7") (pintype "power_in"))
    )
    (net (code "101") (name "Net-(U16-O2)") (class "Default")
      (node (ref "J26") (pin "3") (pinfunction "3_3") (pintype "passive"))
      (node (ref "U16") (pin "6") (pinfunction "O2_6") (pintype "power_in"))
    )
    (net (code "102") (name "Net-(U16-VDD)") (class "Default")
      (node (ref "J26") (pin "1") (pinfunction "1_1") (pintype "passive"))
      (node (ref "J27") (pin "2") (pinfunction "2_2") (pintype "passive"))
      (node (ref "U16") (pin "8") (pinfunction "VDD_8") (pintype "power_in"))
    )
    (net (code "103") (name "unconnected-(J1-Pad01)") (class "Default")
      (node (ref "J1") (pin "01") (pinfunction "01_01") (pintype "passive"))
    )
    (net (code "104") (name "unconnected-(J1-Pad03)") (class "Default")
      (node (ref "J1") (pin "03") (pinfunction "03_03") (pintype "passive"))
    )
    (net (code "105") (name "unconnected-(J1-Pad05)") (class "Default")
      (node (ref "J1") (pin "05") (pinfunction "05_05") (pintype "passive"))
    )
    (net (code "106") (name "unconnected-(J1-Pad07)") (class "Default")
      (node (ref "J1") (pin "07") (pinfunction "07_07") (pintype "passive"))
    )
    (net (code "107") (name "unconnected-(J1-Pad08)") (class "Default")
      (node (ref "J1") (pin "08") (pinfunction "08_08") (pintype "passive"))
    )
    (net (code "108") (name "unconnected-(J1-Pad10)") (class "Default")
      (node (ref "J1") (pin "10") (pinfunction "10_10") (pintype "passive"))
    )
    (net (code "109") (name "unconnected-(J1-Pad12)") (class "Default")
      (node (ref "J1") (pin "12") (pinfunction "12_12") (pintype "passive"))
    )
    (net (code "110") (name "unconnected-(J1-Pad26)") (class "Default")
      (node (ref "J1") (pin "26") (pinfunction "26_26") (pintype "passive"))
    )
    (net (code "111") (name "unconnected-(J1-Pad27)") (class "Default")
      (node (ref "J1") (pin "27") (pinfunction "27_27") (pintype "passive"))
    )
    (net (code "112") (name "unconnected-(J1-Pad28)") (class "Default")
      (node (ref "J1") (pin "28") (pinfunction "28_28") (pintype "passive"))
    )
    (net (code "113") (name "unconnected-(J1-Pad38)") (class "Default")
      (node (ref "J1") (pin "38") (pinfunction "38_38") (pintype "passive"))
    )
    (net (code "114") (name "unconnected-(J7-Pad15)") (class "Default")
      (node (ref "J7") (pin "15") (pinfunction "15_15") (pintype "passive"))
    )
    (net (code "115") (name "unconnected-(J7-Pad17)") (class "Default")
      (node (ref "J7") (pin "17") (pinfunction "17_17") (pintype "passive"))
    )
    (net (code "116") (name "unconnected-(J8-Pad12)") (class "Default")
      (node (ref "J8") (pin "12") (pinfunction "12_12") (pintype "passive"))
    )
    (net (code "117") (name "unconnected-(J8-Pad13)") (class "Default")
      (node (ref "J8") (pin "13") (pinfunction "13_13") (pintype "passive"))
    )
    (net (code "118") (name "unconnected-(J8-Pad15)") (class "Default")
      (node (ref "J8") (pin "15") (pinfunction "15_15") (pintype "passive"))
    )
    (net (code "119") (name "unconnected-(J8-Pad16)") (class "Default")
      (node (ref "J8") (pin "16") (pinfunction "16_16") (pintype "passive"))
    )
    (net (code "120") (name "unconnected-(J8-Pad17)") (class "Default")
      (node (ref "J8") (pin "17") (pinfunction "17_17") (pintype "passive"))
    )
    (net (code "121") (name "unconnected-(J8-Pad18)") (class "Default")
      (node (ref "J8") (pin "18") (pinfunction "18_18") (pintype "passive"))
    )
    (net (code "122") (name "unconnected-(J8-Pad19)") (class "Default")
      (node (ref "J8") (pin "19") (pinfunction "19_19") (pintype "passive"))
    )
    (net (code "123") (name "unconnected-(J8-Pad22)") (class "Default")
      (node (ref "J8") (pin "22") (pinfunction "22_22") (pintype "passive"))
    )
    (net (code "124") (name "unconnected-(J8-Pad23)") (class "Default")
      (node (ref "J8") (pin "23") (pinfunction "23_23") (pintype "passive"))
    )
    (net (code "125") (name "unconnected-(J8-Pad24)") (class "Default")
      (node (ref "J8") (pin "24") (pinfunction "24_24") (pintype "passive"))
    )
    (net (code "126") (name "unconnected-(J9-Pad6)") (class "Default")
      (node (ref "J9") (pin "6") (pinfunction "6_6") (pintype "passive"))
    )
    (net (code "127") (name "unconnected-(J9-Pad7)") (class "Default")
      (node (ref "J9") (pin "7") (pinfunction "7_7") (pintype "passive"))
    )
    (net (code "128") (name "unconnected-(J9-Pad8)") (class "Default")
      (node (ref "J9") (pin "8") (pinfunction "8_8") (pintype "passive"))
    )
    (net (code "129") (name "unconnected-(J9-Pad9)") (class "Default")
      (node (ref "J9") (pin "9") (pinfunction "9_9") (pintype "passive"))
    )
    (net (code "130") (name "unconnected-(J10-Pad6)") (class "Default")
      (node (ref "J10") (pin "6") (pinfunction "6_6") (pintype "passive"))
    )
    (net (code "131") (name "unconnected-(J10-Pad7)") (class "Default")
      (node (ref "J10") (pin "7") (pinfunction "7_7") (pintype "passive"))
    )
    (net (code "132") (name "unconnected-(J10-Pad8)") (class "Default")
      (node (ref "J10") (pin "8") (pinfunction "8_8") (pintype "passive"))
    )
    (net (code "133") (name "unconnected-(J10-Pad9)") (class "Default")
      (node (ref "J10") (pin "9") (pinfunction "9_9") (pintype "passive"))
    )
    (net (code "134") (name "unconnected-(J15-Pad1)") (class "Default")
      (node (ref "J15") (pin "1") (pinfunction "1_1") (pintype "passive"))
    )
    (net (code "135") (name "unconnected-(PS1-NC-Pad8)") (class "Default")
      (node (ref "PS1") (pin "8") (pinfunction "NC_8") (pintype "passive"))
    )
    (net (code "136") (name "unconnected-(U5-A2-Pad4)") (class "Default")
      (node (ref "U5") (pin "4") (pinfunction "A2_4") (pintype "power_in"))
    )
    (net (code "137") (name "unconnected-(U5-C2-Pad3)") (class "Default")
      (node (ref "U5") (pin "3") (pinfunction "C2_3") (pintype "power_in"))
    )
    (net (code "138") (name "unconnected-(U5-O2-Pad6)") (class "Default")
      (node (ref "U5") (pin "6") (pinfunction "O2_6") (pintype "power_in"))
    )
  )
)
